# AD_0.net
KiCad netlist of a schematic drawn in Altium Designer
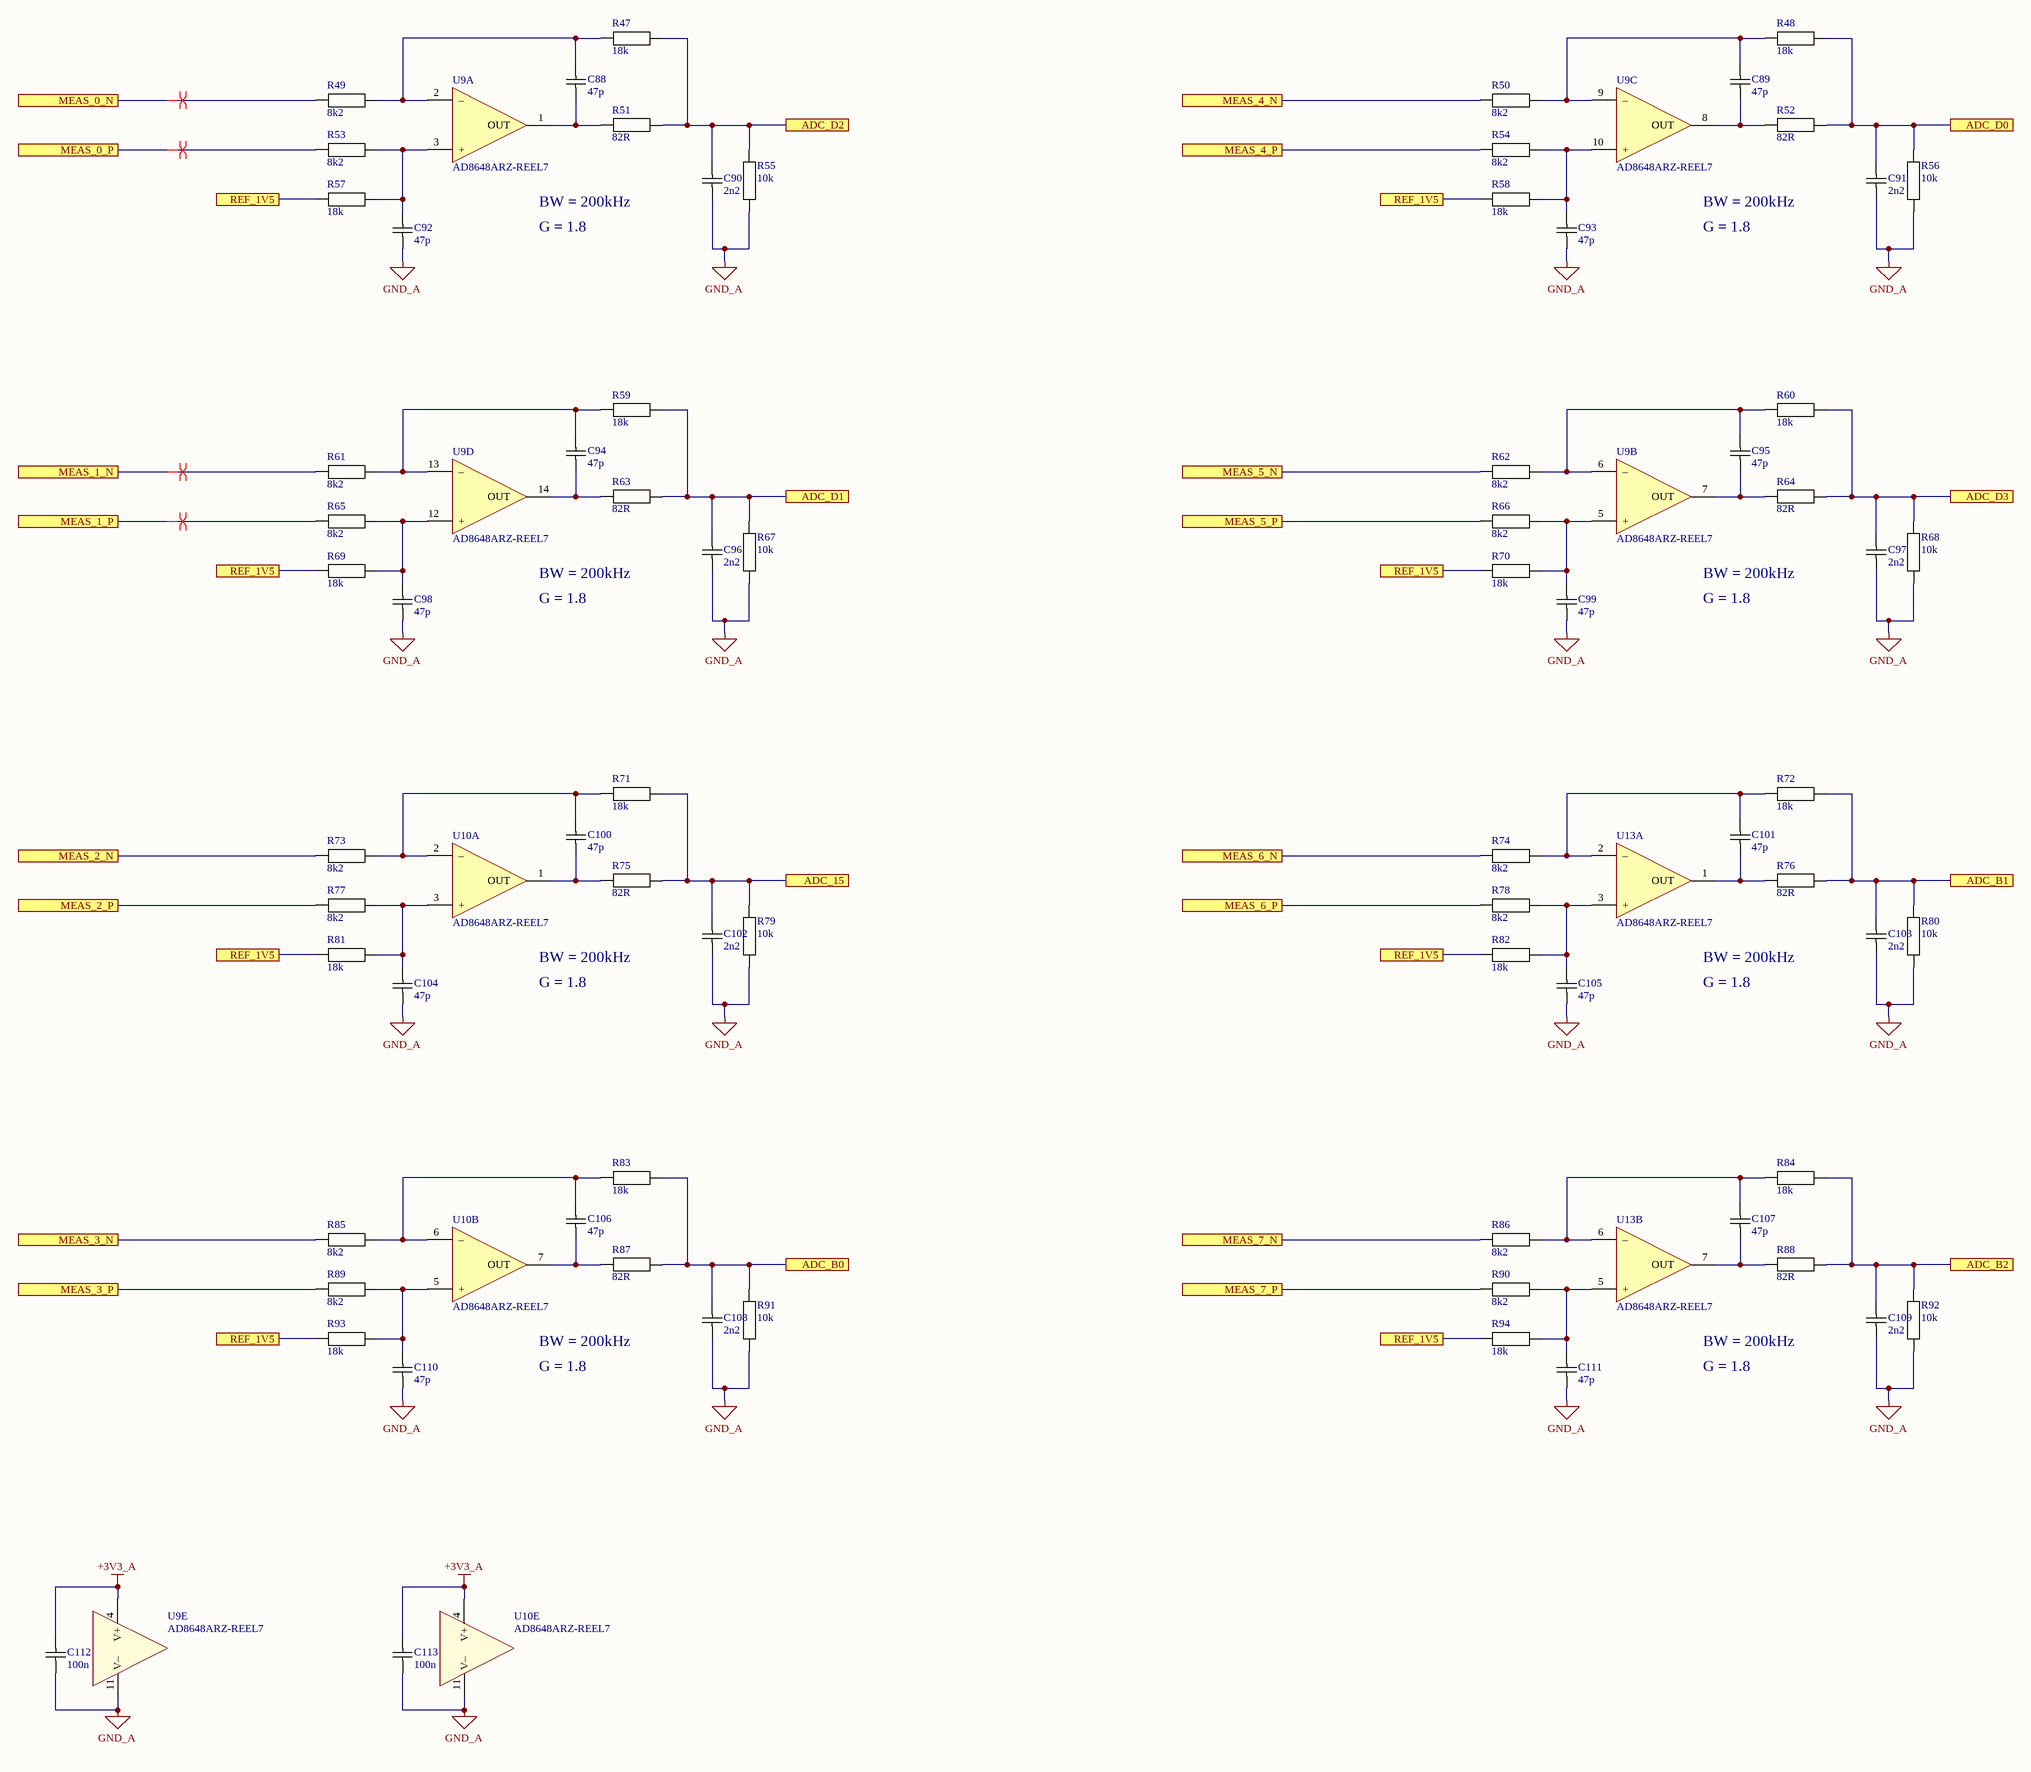
[diagram p0: AD_0.SchDoc]

(export (version "E")
  (design (tool "Eeschema 10.0.6"))
  (components
    (comp (ref "C88")
      (value "47p")
      (footprint "CAPACITOR 1608 REFLOW")
      (description "Capacitor X7R 10% 50V 1608(0603)")
      (libsource (lib "Capacitor") (part "Capacitor"))
    )
    (comp (ref "C89")
      (value "47p")
      (footprint "CAPACITOR 1608 REFLOW")
      (description "Capacitor X7R 10% 50V 1608(0603)")
      (libsource (lib "Capacitor") (part "Capacitor"))
    )
    (comp (ref "C90")
      (value "2n2")
      (footprint "CAPACITOR 1608 REFLOW")
      (description "Capacitor X7R 10% 50V 1608(0603)")
      (libsource (lib "Capacitor") (part "Capacitor"))
    )
    (comp (ref "C91")
      (value "2n2")
      (footprint "CAPACITOR 1608 REFLOW")
      (description "Capacitor X7R 10% 50V 1608(0603)")
      (libsource (lib "Capacitor") (part "Capacitor"))
    )
    (comp (ref "C92")
      (value "47p")
      (footprint "CAPACITOR 1608 REFLOW")
      (description "Capacitor X7R 10% 50V 1608(0603)")
      (libsource (lib "Capacitor") (part "Capacitor"))
    )
    (comp (ref "C93")
      (value "47p")
      (footprint "CAPACITOR 1608 REFLOW")
      (description "Capacitor X7R 10% 50V 1608(0603)")
      (libsource (lib "Capacitor") (part "Capacitor"))
    )
    (comp (ref "C94")
      (value "47p")
      (footprint "CAPACITOR 1608 REFLOW")
      (description "Capacitor X7R 10% 50V 1608(0603)")
      (libsource (lib "Capacitor") (part "Capacitor"))
    )
    (comp (ref "C95")
      (value "47p")
      (footprint "CAPACITOR 1608 REFLOW")
      (description "Capacitor X7R 10% 50V 1608(0603)")
      (libsource (lib "Capacitor") (part "Capacitor"))
    )
    (comp (ref "C96")
      (value "2n2")
      (footprint "CAPACITOR 1608 REFLOW")
      (description "Capacitor X7R 10% 50V 1608(0603)")
      (libsource (lib "Capacitor") (part "Capacitor"))
    )
    (comp (ref "C97")
      (value "2n2")
      (footprint "CAPACITOR 1608 REFLOW")
      (description "Capacitor X7R 10% 50V 1608(0603)")
      (libsource (lib "Capacitor") (part "Capacitor"))
    )
    (comp (ref "C98")
      (value "47p")
      (footprint "CAPACITOR 1608 REFLOW")
      (description "Capacitor X7R 10% 50V 1608(0603)")
      (libsource (lib "Capacitor") (part "Capacitor"))
    )
    (comp (ref "C99")
      (value "47p")
      (footprint "CAPACITOR 1608 REFLOW")
      (description "Capacitor X7R 10% 50V 1608(0603)")
      (libsource (lib "Capacitor") (part "Capacitor"))
    )
    (comp (ref "C100")
      (value "47p")
      (footprint "CAPACITOR 1608 REFLOW")
      (description "Capacitor X7R 10% 50V 1608(0603)")
      (libsource (lib "Capacitor") (part "Capacitor"))
    )
    (comp (ref "C101")
      (value "47p")
      (footprint "CAPACITOR 1608 REFLOW")
      (description "Capacitor X7R 10% 50V 1608(0603)")
      (libsource (lib "Capacitor") (part "Capacitor"))
    )
    (comp (ref "C102")
      (value "2n2")
      (footprint "CAPACITOR 1608 REFLOW")
      (description "Capacitor X7R 10% 50V 1608(0603)")
      (libsource (lib "Capacitor") (part "Capacitor"))
    )
    (comp (ref "C103")
      (value "2n2")
      (footprint "CAPACITOR 1608 REFLOW")
      (description "Capacitor X7R 10% 50V 1608(0603)")
      (libsource (lib "Capacitor") (part "Capacitor"))
    )
    (comp (ref "C104")
      (value "47p")
      (footprint "CAPACITOR 1608 REFLOW")
      (description "Capacitor X7R 10% 50V 1608(0603)")
      (libsource (lib "Capacitor") (part "Capacitor"))
    )
    (comp (ref "C105")
      (value "47p")
      (footprint "CAPACITOR 1608 REFLOW")
      (description "Capacitor X7R 10% 50V 1608(0603)")
      (libsource (lib "Capacitor") (part "Capacitor"))
    )
    (comp (ref "C106")
      (value "47p")
      (footprint "CAPACITOR 1608 REFLOW")
      (description "Capacitor X7R 10% 50V 1608(0603)")
      (libsource (lib "Capacitor") (part "Capacitor"))
    )
    (comp (ref "C107")
      (value "47p")
      (footprint "CAPACITOR 1608 REFLOW")
      (description "Capacitor X7R 10% 50V 1608(0603)")
      (libsource (lib "Capacitor") (part "Capacitor"))
    )
    (comp (ref "C108")
      (value "2n2")
      (footprint "CAPACITOR 1608 REFLOW")
      (description "Capacitor X7R 10% 50V 1608(0603)")
      (libsource (lib "Capacitor") (part "Capacitor"))
    )
    (comp (ref "C109")
      (value "2n2")
      (footprint "CAPACITOR 1608 REFLOW")
      (description "Capacitor X7R 10% 50V 1608(0603)")
      (libsource (lib "Capacitor") (part "Capacitor"))
    )
    (comp (ref "C110")
      (value "47p")
      (footprint "CAPACITOR 1608 REFLOW")
      (description "Capacitor X7R 10% 50V 1608(0603)")
      (libsource (lib "Capacitor") (part "Capacitor"))
    )
    (comp (ref "C111")
      (value "47p")
      (footprint "CAPACITOR 1608 REFLOW")
      (description "Capacitor X7R 10% 50V 1608(0603)")
      (libsource (lib "Capacitor") (part "Capacitor"))
    )
    (comp (ref "C112")
      (value "100n")
      (footprint "CAPACITOR 1608 REFLOW")
      (description "Capacitor X7R 10% 50V 1608(0603)")
      (libsource (lib "Capacitor") (part "Capacitor"))
    )
    (comp (ref "C113")
      (value "100n")
      (footprint "CAPACITOR 1608 REFLOW")
      (description "Capacitor X7R 10% 50V 1608(0603)")
      (libsource (lib "Capacitor") (part "Capacitor"))
    )
    (comp (ref "R47")
      (value "18k")
      (footprint "RESISTOR 1608 REFLOW")
      (description "Resistor 1% 50V 100mW 1608(0603)")
      (libsource (lib "Resistor") (part "Resistor"))
    )
    (comp (ref "R48")
      (value "18k")
      (footprint "RESISTOR 1608 REFLOW")
      (description "Resistor 1% 50V 100mW 1608(0603)")
      (libsource (lib "Resistor") (part "Resistor"))
    )
    (comp (ref "R49")
      (value "8k2")
      (footprint "RESISTOR 1608 REFLOW")
      (description "Resistor 1% 50V 100mW 1608(0603)")
      (libsource (lib "Resistor") (part "Resistor"))
    )
    (comp (ref "R50")
      (value "8k2")
      (footprint "RESISTOR 1608 REFLOW")
      (description "Resistor 1% 50V 100mW 1608(0603)")
      (libsource (lib "Resistor") (part "Resistor"))
    )
    (comp (ref "R51")
      (value "82R")
      (footprint "RESISTOR 1608 REFLOW")
      (description "Resistor 1% 50V 100mW 1608(0603)")
      (libsource (lib "Resistor") (part "Resistor"))
    )
    (comp (ref "R52")
      (value "82R")
      (footprint "RESISTOR 1608 REFLOW")
      (description "Resistor 1% 50V 100mW 1608(0603)")
      (libsource (lib "Resistor") (part "Resistor"))
    )
    (comp (ref "R53")
      (value "8k2")
      (footprint "RESISTOR 1608 REFLOW")
      (description "Resistor 1% 50V 100mW 1608(0603)")
      (libsource (lib "Resistor") (part "Resistor"))
    )
    (comp (ref "R54")
      (value "8k2")
      (footprint "RESISTOR 1608 REFLOW")
      (description "Resistor 1% 50V 100mW 1608(0603)")
      (libsource (lib "Resistor") (part "Resistor"))
    )
    (comp (ref "R55")
      (value "10k")
      (footprint "RESISTOR 1608 REFLOW")
      (description "Resistor 1% 50V 100mW 1608(0603)")
      (libsource (lib "Resistor") (part "Resistor"))
    )
    (comp (ref "R56")
      (value "10k")
      (footprint "RESISTOR 1608 REFLOW")
      (description "Resistor 1% 50V 100mW 1608(0603)")
      (libsource (lib "Resistor") (part "Resistor"))
    )
    (comp (ref "R57")
      (value "18k")
      (footprint "RESISTOR 1608 REFLOW")
      (description "Resistor 1% 50V 100mW 1608(0603)")
      (libsource (lib "Resistor") (part "Resistor"))
    )
    (comp (ref "R58")
      (value "18k")
      (footprint "RESISTOR 1608 REFLOW")
      (description "Resistor 1% 50V 100mW 1608(0603)")
      (libsource (lib "Resistor") (part "Resistor"))
    )
    (comp (ref "R59")
      (value "18k")
      (footprint "RESISTOR 1608 REFLOW")
      (description "Resistor 1% 50V 100mW 1608(0603)")
      (libsource (lib "Resistor") (part "Resistor"))
    )
    (comp (ref "R60")
      (value "18k")
      (footprint "RESISTOR 1608 REFLOW")
      (description "Resistor 1% 50V 100mW 1608(0603)")
      (libsource (lib "Resistor") (part "Resistor"))
    )
    (comp (ref "R61")
      (value "8k2")
      (footprint "RESISTOR 1608 REFLOW")
      (description "Resistor 1% 50V 100mW 1608(0603)")
      (libsource (lib "Resistor") (part "Resistor"))
    )
    (comp (ref "R62")
      (value "8k2")
      (footprint "RESISTOR 1608 REFLOW")
      (description "Resistor 1% 50V 100mW 1608(0603)")
      (libsource (lib "Resistor") (part "Resistor"))
    )
    (comp (ref "R63")
      (value "82R")
      (footprint "RESISTOR 1608 REFLOW")
      (description "Resistor 1% 50V 100mW 1608(0603)")
      (libsource (lib "Resistor") (part "Resistor"))
    )
    (comp (ref "R64")
      (value "82R")
      (footprint "RESISTOR 1608 REFLOW")
      (description "Resistor 1% 50V 100mW 1608(0603)")
      (libsource (lib "Resistor") (part "Resistor"))
    )
    (comp (ref "R65")
      (value "8k2")
      (footprint "RESISTOR 1608 REFLOW")
      (description "Resistor 1% 50V 100mW 1608(0603)")
      (libsource (lib "Resistor") (part "Resistor"))
    )
    (comp (ref "R66")
      (value "8k2")
      (footprint "RESISTOR 1608 REFLOW")
      (description "Resistor 1% 50V 100mW 1608(0603)")
      (libsource (lib "Resistor") (part "Resistor"))
    )
    (comp (ref "R67")
      (value "10k")
      (footprint "RESISTOR 1608 REFLOW")
      (description "Resistor 1% 50V 100mW 1608(0603)")
      (libsource (lib "Resistor") (part "Resistor"))
    )
    (comp (ref "R68")
      (value "10k")
      (footprint "RESISTOR 1608 REFLOW")
      (description "Resistor 1% 50V 100mW 1608(0603)")
      (libsource (lib "Resistor") (part "Resistor"))
    )
    (comp (ref "R69")
      (value "18k")
      (footprint "RESISTOR 1608 REFLOW")
      (description "Resistor 1% 50V 100mW 1608(0603)")
      (libsource (lib "Resistor") (part "Resistor"))
    )
    (comp (ref "R70")
      (value "18k")
      (footprint "RESISTOR 1608 REFLOW")
      (description "Resistor 1% 50V 100mW 1608(0603)")
      (libsource (lib "Resistor") (part "Resistor"))
    )
    (comp (ref "R71")
      (value "18k")
      (footprint "RESISTOR 1608 REFLOW")
      (description "Resistor 1% 50V 100mW 1608(0603)")
      (libsource (lib "Resistor") (part "Resistor"))
    )
    (comp (ref "R72")
      (value "18k")
      (footprint "RESISTOR 1608 REFLOW")
      (description "Resistor 1% 50V 100mW 1608(0603)")
      (libsource (lib "Resistor") (part "Resistor"))
    )
    (comp (ref "R73")
      (value "8k2")
      (footprint "RESISTOR 1608 REFLOW")
      (description "Resistor 1% 50V 100mW 1608(0603)")
      (libsource (lib "Resistor") (part "Resistor"))
    )
    (comp (ref "R74")
      (value "8k2")
      (footprint "RESISTOR 1608 REFLOW")
      (description "Resistor 1% 50V 100mW 1608(0603)")
      (libsource (lib "Resistor") (part "Resistor"))
    )
    (comp (ref "R75")
      (value "82R")
      (footprint "RESISTOR 1608 REFLOW")
      (description "Resistor 1% 50V 100mW 1608(0603)")
      (libsource (lib "Resistor") (part "Resistor"))
    )
    (comp (ref "R76")
      (value "82R")
      (footprint "RESISTOR 1608 REFLOW")
      (description "Resistor 1% 50V 100mW 1608(0603)")
      (libsource (lib "Resistor") (part "Resistor"))
    )
    (comp (ref "R77")
      (value "8k2")
      (footprint "RESISTOR 1608 REFLOW")
      (description "Resistor 1% 50V 100mW 1608(0603)")
      (libsource (lib "Resistor") (part "Resistor"))
    )
    (comp (ref "R78")
      (value "8k2")
      (footprint "RESISTOR 1608 REFLOW")
      (description "Resistor 1% 50V 100mW 1608(0603)")
      (libsource (lib "Resistor") (part "Resistor"))
    )
    (comp (ref "R79")
      (value "10k")
      (footprint "RESISTOR 1608 REFLOW")
      (description "Resistor 1% 50V 100mW 1608(0603)")
      (libsource (lib "Resistor") (part "Resistor"))
    )
    (comp (ref "R80")
      (value "10k")
      (footprint "RESISTOR 1608 REFLOW")
      (description "Resistor 1% 50V 100mW 1608(0603)")
      (libsource (lib "Resistor") (part "Resistor"))
    )
    (comp (ref "R81")
      (value "18k")
      (footprint "RESISTOR 1608 REFLOW")
      (description "Resistor 1% 50V 100mW 1608(0603)")
      (libsource (lib "Resistor") (part "Resistor"))
    )
    (comp (ref "R82")
      (value "18k")
      (footprint "RESISTOR 1608 REFLOW")
      (description "Resistor 1% 50V 100mW 1608(0603)")
      (libsource (lib "Resistor") (part "Resistor"))
    )
    (comp (ref "R83")
      (value "18k")
      (footprint "RESISTOR 1608 REFLOW")
      (description "Resistor 1% 50V 100mW 1608(0603)")
      (libsource (lib "Resistor") (part "Resistor"))
    )
    (comp (ref "R84")
      (value "18k")
      (footprint "RESISTOR 1608 REFLOW")
      (description "Resistor 1% 50V 100mW 1608(0603)")
      (libsource (lib "Resistor") (part "Resistor"))
    )
    (comp (ref "R85")
      (value "8k2")
      (footprint "RESISTOR 1608 REFLOW")
      (description "Resistor 1% 50V 100mW 1608(0603)")
      (libsource (lib "Resistor") (part "Resistor"))
    )
    (comp (ref "R86")
      (value "8k2")
      (footprint "RESISTOR 1608 REFLOW")
      (description "Resistor 1% 50V 100mW 1608(0603)")
      (libsource (lib "Resistor") (part "Resistor"))
    )
    (comp (ref "R87")
      (value "82R")
      (footprint "RESISTOR 1608 REFLOW")
      (description "Resistor 1% 50V 100mW 1608(0603)")
      (libsource (lib "Resistor") (part "Resistor"))
    )
    (comp (ref "R88")
      (value "82R")
      (footprint "RESISTOR 1608 REFLOW")
      (description "Resistor 1% 50V 100mW 1608(0603)")
      (libsource (lib "Resistor") (part "Resistor"))
    )
    (comp (ref "R89")
      (value "8k2")
      (footprint "RESISTOR 1608 REFLOW")
      (description "Resistor 1% 50V 100mW 1608(0603)")
      (libsource (lib "Resistor") (part "Resistor"))
    )
    (comp (ref "R90")
      (value "8k2")
      (footprint "RESISTOR 1608 REFLOW")
      (description "Resistor 1% 50V 100mW 1608(0603)")
      (libsource (lib "Resistor") (part "Resistor"))
    )
    (comp (ref "R91")
      (value "10k")
      (footprint "RESISTOR 1608 REFLOW")
      (description "Resistor 1% 50V 100mW 1608(0603)")
      (libsource (lib "Resistor") (part "Resistor"))
    )
    (comp (ref "R92")
      (value "10k")
      (footprint "RESISTOR 1608 REFLOW")
      (description "Resistor 1% 50V 100mW 1608(0603)")
      (libsource (lib "Resistor") (part "Resistor"))
    )
    (comp (ref "R93")
      (value "18k")
      (footprint "RESISTOR 1608 REFLOW")
      (description "Resistor 1% 50V 100mW 1608(0603)")
      (libsource (lib "Resistor") (part "Resistor"))
    )
    (comp (ref "R94")
      (value "18k")
      (footprint "RESISTOR 1608 REFLOW")
      (description "Resistor 1% 50V 100mW 1608(0603)")
      (libsource (lib "Resistor") (part "Resistor"))
    )
    (comp (ref "U9")
      (value "AD8648ARZ-REEL7")
      (footprint "SO14 P1.27 C4.0X8.8 H1.75")
      (description "Generic quad OPA 14 pins")
      (fields (field (name "MANUFACTURER") "Analog Devices"))
      (libsource (lib "Amplifier") (part "OPA QUAD"))
    )
    (comp (ref "U10")
      (value "AD8648ARZ-REEL7")
      (footprint "SO14 P1.27 C4.0X8.8 H1.75")
      (description "Generic quad OPA 14 pins")
      (fields (field (name "MANUFACTURER") "Analog Devices"))
      (libsource (lib "Amplifier") (part "OPA QUAD"))
    )
    (comp (ref "U13")
      (value "AD8648ARZ-REEL7")
      (footprint "SO14 P1.27 C4.0X8.8 H1.75")
      (description "Generic quad OPA 14 pins")
      (fields (field (name "MANUFACTURER") "Analog Devices"))
      (libsource (lib "Amplifier") (part "OPA QUAD"))
    )
  )
  (nets
    (net (code "1") (name "+3V3_A") (class "Default")
      (node (ref "C112") (pin "2") (pinfunction "2_2") (pintype "passive"))
      (node (ref "C113") (pin "2") (pinfunction "2_2") (pintype "passive"))
      (node (ref "U10") (pin "4") (pinfunction "V+_4") (pintype "passive"))
      (node (ref "U9") (pin "4") (pinfunction "V+_4") (pintype "passive"))
    )
    (net (code "2") (name "/ADC_15") (class "Default")
      (node (ref "C102") (pin "2") (pinfunction "2_2") (pintype "passive"))
      (node (ref "R71") (pin "2") (pinfunction "2_2") (pintype "passive"))
      (node (ref "R75") (pin "2") (pinfunction "2_2") (pintype "passive"))
      (node (ref "R79") (pin "1") (pinfunction "1_1") (pintype "passive"))
    )
    (net (code "3") (name "/ADC_B0") (class "Default")
      (node (ref "C108") (pin "2") (pinfunction "2_2") (pintype "passive"))
      (node (ref "R83") (pin "2") (pinfunction "2_2") (pintype "passive"))
      (node (ref "R87") (pin "2") (pinfunction "2_2") (pintype "passive"))
      (node (ref "R91") (pin "1") (pinfunction "1_1") (pintype "passive"))
    )
    (net (code "4") (name "/ADC_B1") (class "Default")
      (node (ref "C103") (pin "2") (pinfunction "2_2") (pintype "passive"))
      (node (ref "R72") (pin "2") (pinfunction "2_2") (pintype "passive"))
      (node (ref "R76") (pin "2") (pinfunction "2_2") (pintype "passive"))
      (node (ref "R80") (pin "1") (pinfunction "1_1") (pintype "passive"))
    )
    (net (code "5") (name "/ADC_B2") (class "Default")
      (node (ref "C109") (pin "2") (pinfunction "2_2") (pintype "passive"))
      (node (ref "R84") (pin "2") (pinfunction "2_2") (pintype "passive"))
      (node (ref "R88") (pin "2") (pinfunction "2_2") (pintype "passive"))
      (node (ref "R92") (pin "1") (pinfunction "1_1") (pintype "passive"))
    )
    (net (code "6") (name "/ADC_D0") (class "Default")
      (node (ref "C91") (pin "2") (pinfunction "2_2") (pintype "passive"))
      (node (ref "R48") (pin "2") (pinfunction "2_2") (pintype "passive"))
      (node (ref "R52") (pin "2") (pinfunction "2_2") (pintype "passive"))
      (node (ref "R56") (pin "1") (pinfunction "1_1") (pintype "passive"))
    )
    (net (code "7") (name "/ADC_D1") (class "Default")
      (node (ref "C96") (pin "2") (pinfunction "2_2") (pintype "passive"))
      (node (ref "R59") (pin "2") (pinfunction "2_2") (pintype "passive"))
      (node (ref "R63") (pin "2") (pinfunction "2_2") (pintype "passive"))
      (node (ref "R67") (pin "1") (pinfunction "1_1") (pintype "passive"))
    )
    (net (code "8") (name "/ADC_D2") (class "Default")
      (node (ref "C90") (pin "2") (pinfunction "2_2") (pintype "passive"))
      (node (ref "R47") (pin "2") (pinfunction "2_2") (pintype "passive"))
      (node (ref "R51") (pin "2") (pinfunction "2_2") (pintype "passive"))
      (node (ref "R55") (pin "1") (pinfunction "1_1") (pintype "passive"))
    )
    (net (code "9") (name "/ADC_D3") (class "Default")
      (node (ref "C97") (pin "2") (pinfunction "2_2") (pintype "passive"))
      (node (ref "R60") (pin "2") (pinfunction "2_2") (pintype "passive"))
      (node (ref "R64") (pin "2") (pinfunction "2_2") (pintype "passive"))
      (node (ref "R68") (pin "1") (pinfunction "1_1") (pintype "passive"))
    )
    (net (code "10") (name "/MEAS_0_N") (class "Default")
      (node (ref "R49") (pin "1") (pinfunction "1_1") (pintype "passive"))
    )
    (net (code "11") (name "/MEAS_0_P") (class "Default")
      (node (ref "R53") (pin "1") (pinfunction "1_1") (pintype "passive"))
    )
    (net (code "12") (name "/MEAS_1_N") (class "Default")
      (node (ref "R61") (pin "1") (pinfunction "1_1") (pintype "passive"))
    )
    (net (code "13") (name "/MEAS_1_P") (class "Default")
      (node (ref "R65") (pin "1") (pinfunction "1_1") (pintype "passive"))
    )
    (net (code "14") (name "/MEAS_2_N") (class "Default")
      (node (ref "R73") (pin "1") (pinfunction "1_1") (pintype "passive"))
    )
    (net (code "15") (name "/MEAS_2_P") (class "Default")
      (node (ref "R77") (pin "1") (pinfunction "1_1") (pintype "passive"))
    )
    (net (code "16") (name "/MEAS_3_N") (class "Default")
      (node (ref "R85") (pin "1") (pinfunction "1_1") (pintype "passive"))
    )
    (net (code "17") (name "/MEAS_3_P") (class "Default")
      (node (ref "R89") (pin "1") (pinfunction "1_1") (pintype "passive"))
    )
    (net (code "18") (name "/MEAS_4_N") (class "Default")
      (node (ref "R50") (pin "1") (pinfunction "1_1") (pintype "passive"))
    )
    (net (code "19") (name "/MEAS_4_P") (class "Default")
      (node (ref "R54") (pin "1") (pinfunction "1_1") (pintype "passive"))
    )
    (net (code "20") (name "/MEAS_5_N") (class "Default")
      (node (ref "R62") (pin "1") (pinfunction "1_1") (pintype "passive"))
    )
    (net (code "21") (name "/MEAS_5_P") (class "Default")
      (node (ref "R66") (pin "1") (pinfunction "1_1") (pintype "passive"))
    )
    (net (code "22") (name "/MEAS_6_N") (class "Default")
      (node (ref "R74") (pin "1") (pinfunction "1_1") (pintype "passive"))
    )
    (net (code "23") (name "/MEAS_6_P") (class "Default")
      (node (ref "R78") (pin "1") (pinfunction "1_1") (pintype "passive"))
    )
    (net (code "24") (name "/MEAS_7_N") (class "Default")
      (node (ref "R86") (pin "1") (pinfunction "1_1") (pintype "passive"))
    )
    (net (code "25") (name "/MEAS_7_P") (class "Default")
      (node (ref "R90") (pin "1") (pinfunction "1_1") (pintype "passive"))
    )
    (net (code "26") (name "/REF_1V5") (class "Default")
      (node (ref "R57") (pin "2") (pinfunction "2_2") (pintype "passive"))
      (node (ref "R58") (pin "2") (pinfunction "2_2") (pintype "passive"))
      (node (ref "R69") (pin "2") (pinfunction "2_2") (pintype "passive"))
      (node (ref "R70") (pin "2") (pinfunction "2_2") (pintype "passive"))
      (node (ref "R81") (pin "2") (pinfunction "2_2") (pintype "passive"))
      (node (ref "R82") (pin "2") (pinfunction "2_2") (pintype "passive"))
      (node (ref "R93") (pin "2") (pinfunction "2_2") (pintype "passive"))
      (node (ref "R94") (pin "2") (pinfunction "2_2") (pintype "passive"))
    )
    (net (code "27") (name "GND_A") (class "Default")
      (node (ref "C102") (pin "1") (pinfunction "1_1") (pintype "passive"))
      (node (ref "C103") (pin "1") (pinfunction "1_1") (pintype "passive"))
      (node (ref "C104") (pin "1") (pinfunction "1_1") (pintype "passive"))
      (node (ref "C105") (pin "1") (pinfunction "1_1") (pintype "passive"))
      (node (ref "C108") (pin "1") (pinfunction "1_1") (pintype "passive"))
      (node (ref "C109") (pin "1") (pinfunction "1_1") (pintype "passive"))
      (node (ref "C110") (pin "1") (pinfunction "1_1") (pintype "passive"))
      (node (ref "C111") (pin "1") (pinfunction "1_1") (pintype "passive"))
      (node (ref "C112") (pin "1") (pinfunction "1_1") (pintype "passive"))
      (node (ref "C113") (pin "1") (pinfunction "1_1") (pintype "passive"))
      (node (ref "C90") (pin "1") (pinfunction "1_1") (pintype "passive"))
      (node (ref "C91") (pin "1") (pinfunction "1_1") (pintype "passive"))
      (node (ref "C92") (pin "1") (pinfunction "1_1") (pintype "passive"))
      (node (ref "C93") (pin "1") (pinfunction "1_1") (pintype "passive"))
      (node (ref "C96") (pin "1") (pinfunction "1_1") (pintype "passive"))
      (node (ref "C97") (pin "1") (pinfunction "1_1") (pintype "passive"))
      (node (ref "C98") (pin "1") (pinfunction "1_1") (pintype "passive"))
      (node (ref "C99") (pin "1") (pinfunction "1_1") (pintype "passive"))
      (node (ref "R55") (pin "2") (pinfunction "2_2") (pintype "passive"))
      (node (ref "R56") (pin "2") (pinfunction "2_2") (pintype "passive"))
      (node (ref "R67") (pin "2") (pinfunction "2_2") (pintype "passive"))
      (node (ref "R68") (pin "2") (pinfunction "2_2") (pintype "passive"))
      (node (ref "R79") (pin "2") (pinfunction "2_2") (pintype "passive"))
      (node (ref "R80") (pin "2") (pinfunction "2_2") (pintype "passive"))
      (node (ref "R91") (pin "2") (pinfunction "2_2") (pintype "passive"))
      (node (ref "R92") (pin "2") (pinfunction "2_2") (pintype "passive"))
      (node (ref "U10") (pin "11") (pinfunction "V–_11") (pintype "passive"))
      (node (ref "U9") (pin "11") (pinfunction "V–_11") (pintype "passive"))
    )
    (net (code "28") (name "Net-(U9A-+)") (class "Default")
      (node (ref "C92") (pin "2") (pinfunction "2_2") (pintype "passive"))
      (node (ref "R53") (pin "2") (pinfunction "2_2") (pintype "passive"))
      (node (ref "R57") (pin "1") (pinfunction "1_1") (pintype "passive"))
      (node (ref "U9") (pin "3") (pinfunction "+_3") (pintype "passive"))
    )
    (net (code "29") (name "Net-(U9A-OUT)") (class "Default")
      (node (ref "C88") (pin "1") (pinfunction "1_1") (pintype "passive"))
      (node (ref "R51") (pin "1") (pinfunction "1_1") (pintype "passive"))
      (node (ref "U9") (pin "1") (pinfunction "OUT_1") (pintype "passive"))
    )
    (net (code "30") (name "Net-(U9A-–)") (class "Default")
      (node (ref "C88") (pin "2") (pinfunction "2_2") (pintype "passive"))
      (node (ref "R47") (pin "1") (pinfunction "1_1") (pintype "passive"))
      (node (ref "R49") (pin "2") (pinfunction "2_2") (pintype "passive"))
      (node (ref "U9") (pin "2") (pinfunction "–_2") (pintype "passive"))
    )
    (net (code "31") (name "Net-(U9B-+)") (class "Default")
      (node (ref "C99") (pin "2") (pinfunction "2_2") (pintype "passive"))
      (node (ref "R66") (pin "2") (pinfunction "2_2") (pintype "passive"))
      (node (ref "R70") (pin "1") (pinfunction "1_1") (pintype "passive"))
      (node (ref "U9") (pin "5") (pinfunction "+_5") (pintype "passive"))
    )
    (net (code "32") (name "Net-(U9B-OUT)") (class "Default")
      (node (ref "C95") (pin "1") (pinfunction "1_1") (pintype "passive"))
      (node (ref "R64") (pin "1") (pinfunction "1_1") (pintype "passive"))
      (node (ref "U9") (pin "7") (pinfunction "OUT_7") (pintype "passive"))
    )
    (net (code "33") (name "Net-(U9B-–)") (class "Default")
      (node (ref "C95") (pin "2") (pinfunction "2_2") (pintype "passive"))
      (node (ref "R60") (pin "1") (pinfunction "1_1") (pintype "passive"))
      (node (ref "R62") (pin "2") (pinfunction "2_2") (pintype "passive"))
      (node (ref "U9") (pin "6") (pinfunction "–_6") (pintype "passive"))
    )
    (net (code "34") (name "Net-(U9C-+)") (class "Default")
      (node (ref "C93") (pin "2") (pinfunction "2_2") (pintype "passive"))
      (node (ref "R54") (pin "2") (pinfunction "2_2") (pintype "passive"))
      (node (ref "R58") (pin "1") (pinfunction "1_1") (pintype "passive"))
      (node (ref "U9") (pin "10") (pinfunction "+_10") (pintype "passive"))
    )
    (net (code "35") (name "Net-(U9C-OUT)") (class "Default")
      (node (ref "C89") (pin "1") (pinfunction "1_1") (pintype "passive"))
      (node (ref "R52") (pin "1") (pinfunction "1_1") (pintype "passive"))
      (node (ref "U9") (pin "8") (pinfunction "OUT_8") (pintype "passive"))
    )
    (net (code "36") (name "Net-(U9C-–)") (class "Default")
      (node (ref "C89") (pin "2") (pinfunction "2_2") (pintype "passive"))
      (node (ref "R48") (pin "1") (pinfunction "1_1") (pintype "passive"))
      (node (ref "R50") (pin "2") (pinfunction "2_2") (pintype "passive"))
      (node (ref "U9") (pin "9") (pinfunction "–_9") (pintype "passive"))
    )
    (net (code "37") (name "Net-(U9D-+)") (class "Default")
      (node (ref "C98") (pin "2") (pinfunction "2_2") (pintype "passive"))
      (node (ref "R65") (pin "2") (pinfunction "2_2") (pintype "passive"))
      (node (ref "R69") (pin "1") (pinfunction "1_1") (pintype "passive"))
      (node (ref "U9") (pin "12") (pinfunction "+_12") (pintype "passive"))
    )
    (net (code "38") (name "Net-(U9D-OUT)") (class "Default")
      (node (ref "C94") (pin "1") (pinfunction "1_1") (pintype "passive"))
      (node (ref "R63") (pin "1") (pinfunction "1_1") (pintype "passive"))
      (node (ref "U9") (pin "14") (pinfunction "OUT_14") (pintype "passive"))
    )
    (net (code "39") (name "Net-(U9D-–)") (class "Default")
      (node (ref "C94") (pin "2") (pinfunction "2_2") (pintype "passive"))
      (node (ref "R59") (pin "1") (pinfunction "1_1") (pintype "passive"))
      (node (ref "R61") (pin "2") (pinfunction "2_2") (pintype "passive"))
      (node (ref "U9") (pin "13") (pinfunction "–_13") (pintype "passive"))
    )
    (net (code "40") (name "Net-(U10A-+)") (class "Default")
      (node (ref "C104") (pin "2") (pinfunction "2_2") (pintype "passive"))
      (node (ref "R77") (pin "2") (pinfunction "2_2") (pintype "passive"))
      (node (ref "R81") (pin "1") (pinfunction "1_1") (pintype "passive"))
      (node (ref "U10") (pin "3") (pinfunction "+_3") (pintype "passive"))
    )
    (net (code "41") (name "Net-(U10A-OUT)") (class "Default")
      (node (ref "C100") (pin "1") (pinfunction "1_1") (pintype "passive"))
      (node (ref "R75") (pin "1") (pinfunction "1_1") (pintype "passive"))
      (node (ref "U10") (pin "1") (pinfunction "OUT_1") (pintype "passive"))
    )
    (net (code "42") (name "Net-(U10A-–)") (class "Default")
      (node (ref "C100") (pin "2") (pinfunction "2_2") (pintype "passive"))
      (node (ref "R71") (pin "1") (pinfunction "1_1") (pintype "passive"))
      (node (ref "R73") (pin "2") (pinfunction "2_2") (pintype "passive"))
      (node (ref "U10") (pin "2") (pinfunction "–_2") (pintype "passive"))
    )
    (net (code "43") (name "Net-(U10B-+)") (class "Default")
      (node (ref "C110") (pin "2") (pinfunction "2_2") (pintype "passive"))
      (node (ref "R89") (pin "2") (pinfunction "2_2") (pintype "passive"))
      (node (ref "R93") (pin "1") (pinfunction "1_1") (pintype "passive"))
      (node (ref "U10") (pin "5") (pinfunction "+_5") (pintype "passive"))
    )
    (net (code "44") (name "Net-(U10B-OUT)") (class "Default")
      (node (ref "C106") (pin "1") (pinfunction "1_1") (pintype "passive"))
      (node (ref "R87") (pin "1") (pinfunction "1_1") (pintype "passive"))
      (node (ref "U10") (pin "7") (pinfunction "OUT_7") (pintype "passive"))
    )
    (net (code "45") (name "Net-(U10B-–)") (class "Default")
      (node (ref "C106") (pin "2") (pinfunction "2_2") (pintype "passive"))
      (node (ref "R83") (pin "1") (pinfunction "1_1") (pintype "passive"))
      (node (ref "R85") (pin "2") (pinfunction "2_2") (pintype "passive"))
      (node (ref "U10") (pin "6") (pinfunction "–_6") (pintype "passive"))
    )
    (net (code "46") (name "Net-(U13A-+)") (class "Default")
      (node (ref "C105") (pin "2") (pinfunction "2_2") (pintype "passive"))
      (node (ref "R78") (pin "2") (pinfunction "2_2") (pintype "passive"))
      (node (ref "R82") (pin "1") (pinfunction "1_1") (pintype "passive"))
      (node (ref "U13") (pin "3") (pinfunction "+_3") (pintype "passive"))
    )
    (net (code "47") (name "Net-(U13A-OUT)") (class "Default")
      (node (ref "C101") (pin "1") (pinfunction "1_1") (pintype "passive"))
      (node (ref "R76") (pin "1") (pinfunction "1_1") (pintype "passive"))
      (node (ref "U13") (pin "1") (pinfunction "OUT_1") (pintype "passive"))
    )
    (net (code "48") (name "Net-(U13A-–)") (class "Default")
      (node (ref "C101") (pin "2") (pinfunction "2_2") (pintype "passive"))
      (node (ref "R72") (pin "1") (pinfunction "1_1") (pintype "passive"))
      (node (ref "R74") (pin "2") (pinfunction "2_2") (pintype "passive"))
      (node (ref "U13") (pin "2") (pinfunction "–_2") (pintype "passive"))
    )
    (net (code "49") (name "Net-(U13B-+)") (class "Default")
      (node (ref "C111") (pin "2") (pinfunction "2_2") (pintype "passive"))
      (node (ref "R90") (pin "2") (pinfunction "2_2") (pintype "passive"))
      (node (ref "R94") (pin "1") (pinfunction "1_1") (pintype "passive"))
      (node (ref "U13") (pin "5") (pinfunction "+_5") (pintype "passive"))
    )
    (net (code "50") (name "Net-(U13B-OUT)") (class "Default")
      (node (ref "C107") (pin "1") (pinfunction "1_1") (pintype "passive"))
      (node (ref "R88") (pin "1") (pinfunction "1_1") (pintype "passive"))
      (node (ref "U13") (pin "7") (pinfunction "OUT_7") (pintype "passive"))
    )
    (net (code "51") (name "Net-(U13B-–)") (class "Default")
      (node (ref "C107") (pin "2") (pinfunction "2_2") (pintype "passive"))
      (node (ref "R84") (pin "1") (pinfunction "1_1") (pintype "passive"))
      (node (ref "R86") (pin "2") (pinfunction "2_2") (pintype "passive"))
      (node (ref "U13") (pin "6") (pinfunction "–_6") (pintype "passive"))
    )
  )
)
